# psu.net
KiCad netlist of a schematic drawn in EAGLE
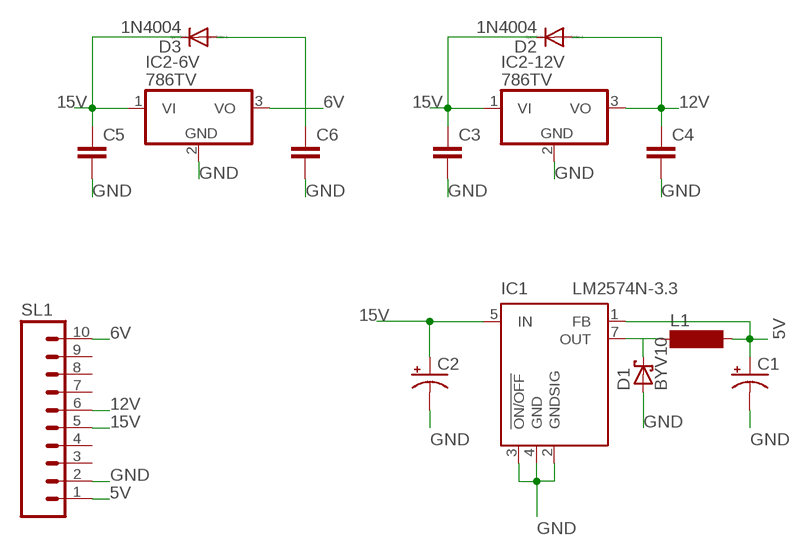
[diagram p0: schematic, sheet 1]

(export (version "E")
  (design (tool "Eeschema 10.0.6"))
  (components
    (comp (ref "C1")
      (value "CPOL-USE5-8.5")
      (footprint "eagle-import:E5-8,5")
      (libsource (lib "eagle-import") (part "CPOL-USE5-8.5"))
    )
    (comp (ref "C2")
      (value "CPOL-USE5-5")
      (footprint "eagle-import:E5-5")
      (libsource (lib "eagle-import") (part "CPOL-USE5-5"))
    )
    (comp (ref "C3")
      (value "C-EU050-030X075")
      (footprint "eagle-import:C050-030X075")
      (libsource (lib "eagle-import") (part "C-EU050-030X075"))
    )
    (comp (ref "C4")
      (value "C-EU050-030X075")
      (footprint "eagle-import:C050-030X075")
      (libsource (lib "eagle-import") (part "C-EU050-030X075"))
    )
    (comp (ref "C5")
      (value "C-EU050-030X075")
      (footprint "eagle-import:C050-030X075")
      (libsource (lib "eagle-import") (part "C-EU050-030X075"))
    )
    (comp (ref "C6")
      (value "C-EU050-030X075")
      (footprint "eagle-import:C050-030X075")
      (libsource (lib "eagle-import") (part "C-EU050-030X075"))
    )
    (comp (ref "D1")
      (value "BYV10")
      (footprint "eagle-import:DO41-10")
      (libsource (lib "eagle-import") (part "BYV10"))
    )
    (comp (ref "D2")
      (value "1N4004")
      (footprint "eagle-import:DO41-10")
      (libsource (lib "eagle-import") (part "1N4004"))
    )
    (comp (ref "D3")
      (value "1N4004")
      (footprint "eagle-import:DO41-10")
      (libsource (lib "eagle-import") (part "1N4004"))
    )
    (comp (ref "IC1")
      (value "LM2574N-3.3")
      (footprint "eagle-import:DIL08")
      (libsource (lib "eagle-import") (part "LM2574?-N3.3"))
    )
    (comp (ref "IC2-6V")
      (value "786TV")
      (footprint "eagle-import:TO220V")
      (libsource (lib "eagle-import") (part "78TV6"))
    )
    (comp (ref "IC2-12V")
      (value "786TV")
      (footprint "eagle-import:TO220V")
      (libsource (lib "eagle-import") (part "78TV6"))
    )
    (comp (ref "L1")
      (value "BS11")
      (footprint "eagle-import:BS11")
      (libsource (lib "eagle-import") (part "BS11"))
    )
    (comp (ref "SL1")
      (value "M10")
      (footprint "eagle-import:10P")
      (libsource (lib "eagle-import") (part "M10"))
    )
  )
  (nets
    (net (code "1") (name "/5V") (class "Default")
      (node (ref "C1") (pin "+") (pinfunction "+_+") (pintype "passive"))
      (node (ref "IC1") (pin "1") (pinfunction "FB_1") (pintype "input"))
      (node (ref "L1") (pin "2") (pinfunction "2_2") (pintype "passive"))
      (node (ref "SL1") (pin "1") (pinfunction "1_1") (pintype "passive"))
    )
    (net (code "2") (name "/6V") (class "Default")
      (node (ref "C6") (pin "1") (pinfunction "1_1") (pintype "passive"))
      (node (ref "D3") (pin "A") (pinfunction "A_A") (pintype "passive"))
      (node (ref "IC2-6V") (pin "3") (pinfunction "VO_3") (pintype "passive"))
      (node (ref "SL1") (pin "10") (pinfunction "10_10") (pintype "passive"))
    )
    (net (code "3") (name "/12V") (class "Default")
      (node (ref "C4") (pin "1") (pinfunction "1_1") (pintype "passive"))
      (node (ref "D2") (pin "A") (pinfunction "A_A") (pintype "passive"))
      (node (ref "IC2-12V") (pin "3") (pinfunction "VO_3") (pintype "passive"))
      (node (ref "SL1") (pin "6") (pinfunction "6_6") (pintype "passive"))
    )
    (net (code "4") (name "/15V") (class "Default")
      (node (ref "C2") (pin "+") (pinfunction "+_+") (pintype "passive"))
      (node (ref "C3") (pin "1") (pinfunction "1_1") (pintype "passive"))
      (node (ref "C5") (pin "1") (pinfunction "1_1") (pintype "passive"))
      (node (ref "D2") (pin "C") (pinfunction "C_C") (pintype "passive"))
      (node (ref "D3") (pin "C") (pinfunction "C_C") (pintype "passive"))
      (node (ref "IC1") (pin "5") (pinfunction "IN_5") (pintype "input"))
      (node (ref "IC2-12V") (pin "1") (pinfunction "VI_1") (pintype "input"))
      (node (ref "IC2-6V") (pin "1") (pinfunction "VI_1") (pintype "input"))
      (node (ref "SL1") (pin "5") (pinfunction "5_5") (pintype "passive"))
    )
    (net (code "5") (name "/GND") (class "Default")
      (node (ref "C1") (pin "-") (pinfunction "-_-") (pintype "passive"))
      (node (ref "C2") (pin "-") (pinfunction "-_-") (pintype "passive"))
      (node (ref "C3") (pin "2") (pinfunction "2_2") (pintype "passive"))
      (node (ref "C4") (pin "2") (pinfunction "2_2") (pintype "passive"))
      (node (ref "C5") (pin "2") (pinfunction "2_2") (pintype "passive"))
      (node (ref "C6") (pin "2") (pinfunction "2_2") (pintype "passive"))
      (node (ref "D1") (pin "A") (pinfunction "A_A") (pintype "passive"))
      (node (ref "IC1") (pin "2") (pinfunction "GNDSIG_2") (pintype "input"))
      (node (ref "IC1") (pin "3") (pinfunction "~{ON/OFF}_3") (pintype "input"))
      (node (ref "IC1") (pin "4") (pinfunction "GND_4") (pintype "power_in"))
      (node (ref "IC2-12V") (pin "2") (pinfunction "GND_2") (pintype "passive"))
      (node (ref "IC2-6V") (pin "2") (pinfunction "GND_2") (pintype "passive"))
      (node (ref "SL1") (pin "2") (pinfunction "2_2") (pintype "passive"))
    )
    (net (code "6") (name "Net-(IC1-OUT)") (class "Default")
      (node (ref "D1") (pin "C") (pinfunction "C_C") (pintype "passive"))
      (node (ref "IC1") (pin "7") (pinfunction "OUT_7") (pintype "passive"))
      (node (ref "L1") (pin "1") (pinfunction "1_1") (pintype "passive"))
    )
    (net (code "7") (name "unconnected-(SL1-Pad3)") (class "Default")
      (node (ref "SL1") (pin "3") (pinfunction "3_3") (pintype "passive"))
    )
    (net (code "8") (name "unconnected-(SL1-Pad4)") (class "Default")
      (node (ref "SL1") (pin "4") (pinfunction "4_4") (pintype "passive"))
    )
    (net (code "9") (name "unconnected-(SL1-Pad7)") (class "Default")
      (node (ref "SL1") (pin "7") (pinfunction "7_7") (pintype "passive"))
    )
    (net (code "10") (name "unconnected-(SL1-Pad8)") (class "Default")
      (node (ref "SL1") (pin "8") (pinfunction "8_8") (pintype "passive"))
    )
    (net (code "11") (name "unconnected-(SL1-Pad9)") (class "Default")
      (node (ref "SL1") (pin "9") (pinfunction "9_9") (pintype "passive"))
    )
  )
)
